# TX.net
KiCad netlist of a schematic drawn in EAGLE
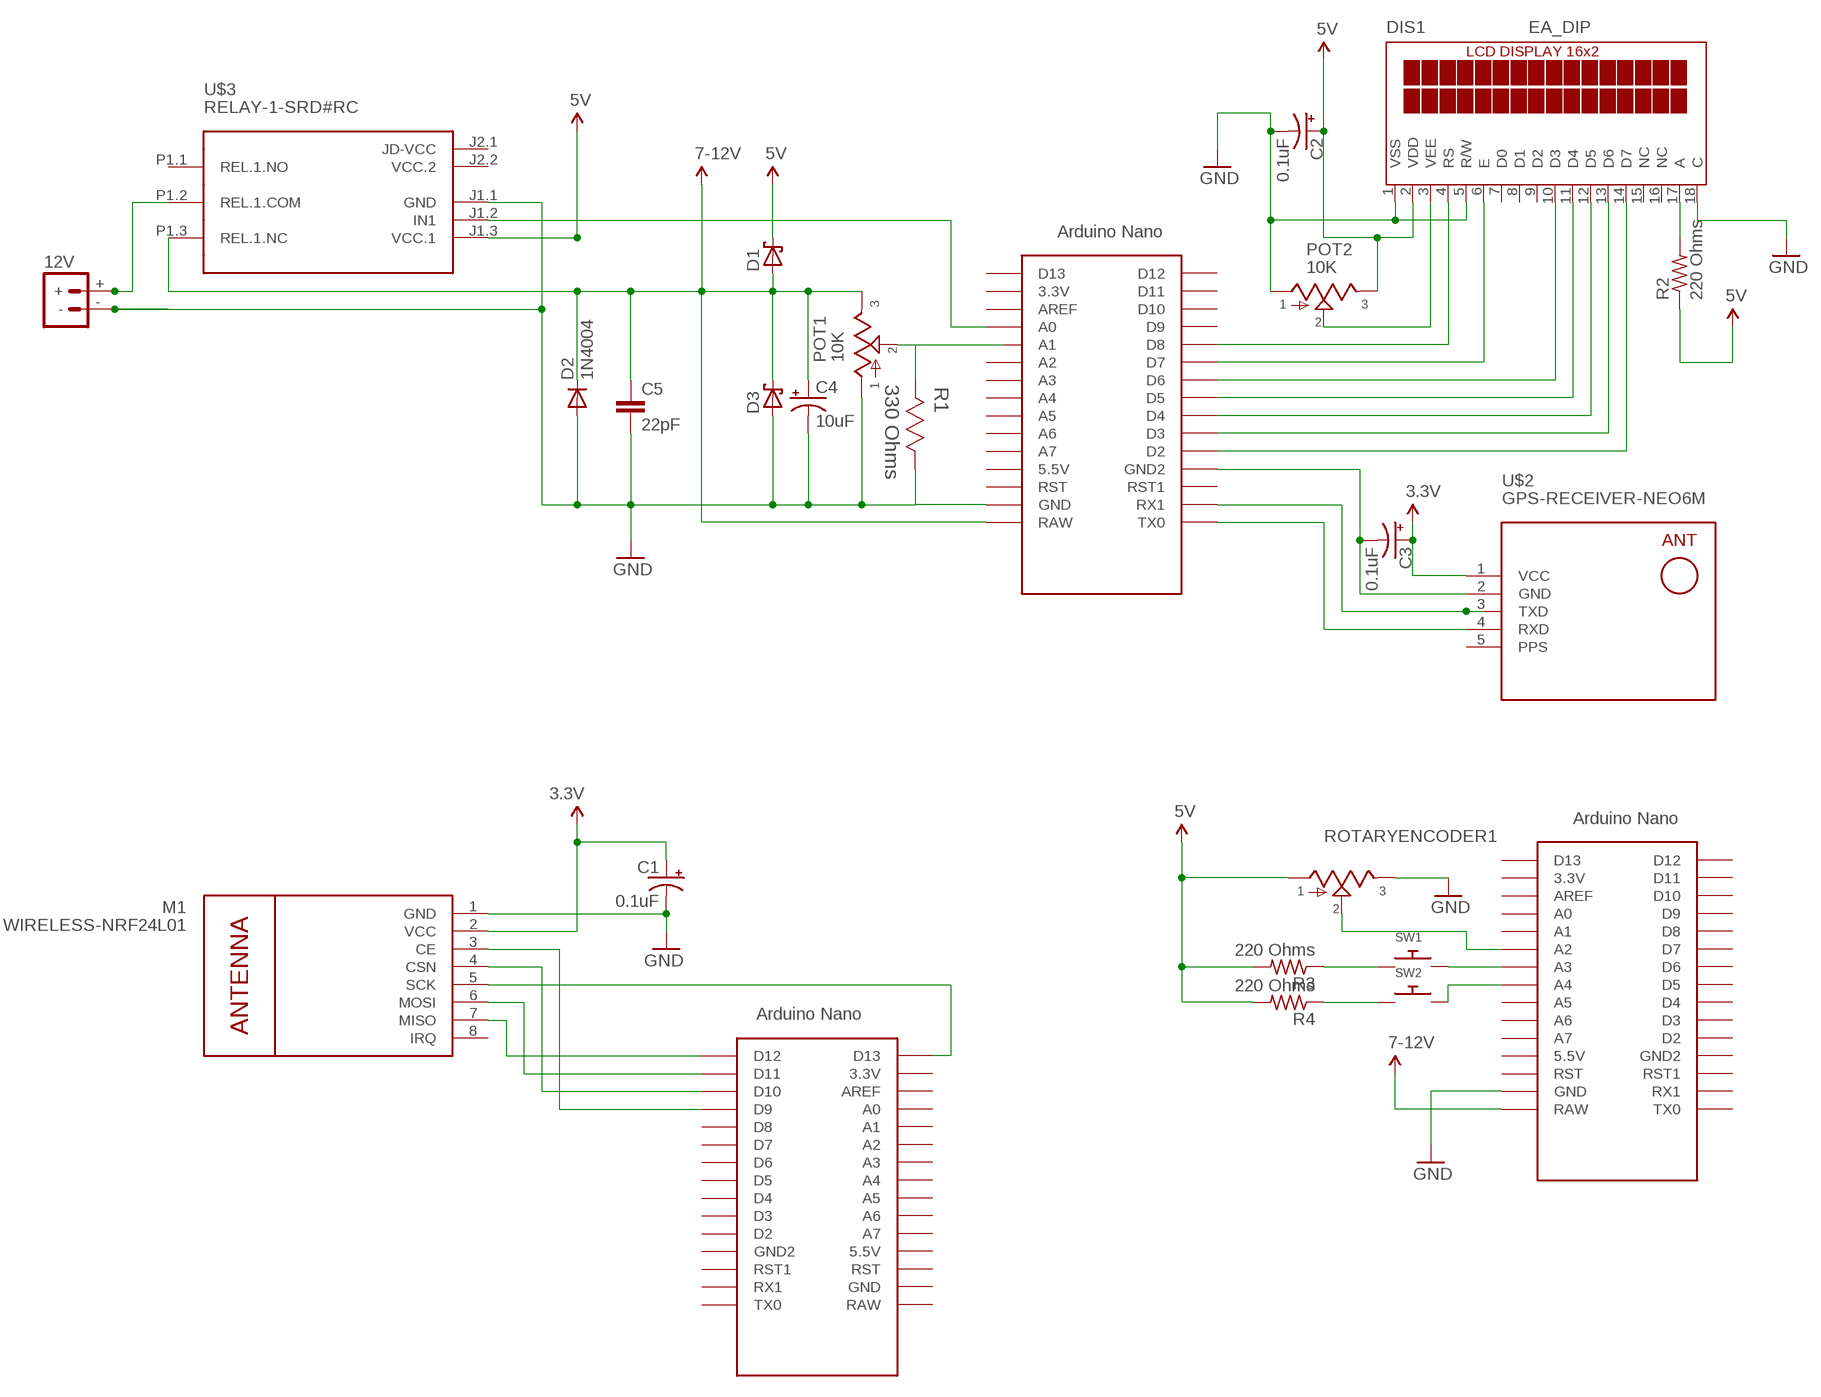
[diagram p0: schematic, sheet 1]

(export (version "E")
  (design (tool "Eeschema 10.0.6"))
  (components
    (comp (ref "12V")
      (value "BATTERY_CONN_DEANS")
      (footprint "eagle-import:DEANS")
      (libsource (lib "eagle-import") (part "BATTERY_CONN_DEANS"))
    )
    (comp (ref "C1")
      (value "0.1uF")
      (footprint "eagle-import:EIA3216")
      (libsource (lib "eagle-import") (part "10UF-16V-10%(TANT)"))
    )
    (comp (ref "C2")
      (value "0.1uF")
      (footprint "eagle-import:EIA3216")
      (libsource (lib "eagle-import") (part "10UF-16V-10%(TANT)"))
    )
    (comp (ref "C3")
      (value "0.1uF")
      (footprint "eagle-import:EIA3216")
      (libsource (lib "eagle-import") (part "10UF-16V-10%(TANT)"))
    )
    (comp (ref "C4")
      (value "10uF")
      (footprint "eagle-import:EIA3216")
      (libsource (lib "eagle-import") (part "10UF-16V-10%(TANT)"))
    )
    (comp (ref "C5")
      (value "22pF")
      (footprint "eagle-import:C2.5-3")
      (libsource (lib "eagle-import") (part "C2,5-3"))
    )
    (comp (ref "D1")
      (value "SCHOTTKY-DIODEAG")
      (footprint "eagle-import:AG")
      (libsource (lib "eagle-import") (part "SCHOTTKY-DIODEAG"))
    )
    (comp (ref "D2")
      (value "1N4004")
      (footprint "eagle-import:DO41-10")
      (libsource (lib "eagle-import") (part "1N4004"))
    )
    (comp (ref "D3")
      (value "SCHOTTKY-DIODEAG")
      (footprint "eagle-import:AG")
      (libsource (lib "eagle-import") (part "SCHOTTKY-DIODEAG"))
    )
    (comp (ref "DIS1")
      (value "EA_DIP")
      (footprint "eagle-import:EA_DIP")
      (libsource (lib "eagle-import") (part "EA_DIP"))
    )
    (comp (ref "M1")
      (value "WIRELESS-NRF24L01")
      (footprint "eagle-import:WIRELESS-NRF24L01")
      (libsource (lib "eagle-import") (part "WIRELESS-NRF24L01"))
    )
    (comp (ref "POT1")
      (value "10K")
      (footprint "eagle-import:POT")
      (libsource (lib "eagle-import") (part "POT"))
    )
    (comp (ref "POT2")
      (value "10K")
      (footprint "eagle-import:POT")
      (libsource (lib "eagle-import") (part "POT"))
    )
    (comp (ref "R1")
      (value "330 Ohms")
      (footprint "eagle-import:RESC1608X60N")
      (fields (field (name "MPN") "CPF0603F44K2C1") (field (name "TOLERANCE") "± 1%"))
      (libsource (lib "eagle-import") (part "CPF0603F44K2C1"))
    )
    (comp (ref "R2")
      (value "220 Ohms")
      (footprint "eagle-import:0204V")
      (libsource (lib "eagle-import") (part "R-US_0204/2V"))
    )
    (comp (ref "R3")
      (value "220 Ohms")
      (footprint "eagle-import:0204V")
      (libsource (lib "eagle-import") (part "R-US_0204/2V"))
    )
    (comp (ref "R4")
      (value "220 Ohms")
      (footprint "eagle-import:0204V")
      (libsource (lib "eagle-import") (part "R-US_0204/2V"))
    )
    (comp (ref "ROTARYENCODER1")
      (value "POT")
      (footprint "eagle-import:POT")
      (libsource (lib "eagle-import") (part "POT"))
    )
    (comp (ref "SW1")
      (value "SWITCH_PUSHBUTTONC&K_KSS")
      (footprint "eagle-import:BTN_CK_KSS")
      (libsource (lib "eagle-import") (part "SWITCH_PUSHBUTTONC&K_KSS"))
    )
    (comp (ref "SW2")
      (value "SWITCH_PUSHBUTTONC&K_KSS")
      (footprint "eagle-import:BTN_CK_KSS")
      (libsource (lib "eagle-import") (part "SWITCH_PUSHBUTTONC&K_KSS"))
    )
    (comp (ref "U$1")
      (value "NANO")
      (footprint "eagle-import:NANO")
      (libsource (lib "eagle-import") (part "NANO"))
    )
    (comp (ref "U$2")
      (value "GPS-RECEIVER-NEO6M")
      (footprint "eagle-import:GPS-RECEIVER-NEO6M")
      (libsource (lib "eagle-import") (part "GPS-RECEIVER-NEO6M"))
    )
    (comp (ref "U$3")
      (value "RELAY-1-SRD#RC")
      (footprint "eagle-import:RELAY-1-SRD#RC")
      (libsource (lib "eagle-import") (part "RELAY-1-SRD#RC"))
    )
    (comp (ref "U$4")
      (value "NANO")
      (footprint "eagle-import:NANO")
      (libsource (lib "eagle-import") (part "NANO"))
    )
    (comp (ref "U$5")
      (value "NANO")
      (footprint "eagle-import:NANO")
      (libsource (lib "eagle-import") (part "NANO"))
    )
  )
  (nets
    (net (code "1") (name "/PPS") (class "Default")
      (node (ref "U$2") (pin "5") (pinfunction "PPS_5") (pintype "power_in"))
    )
    (net (code "2") (name "/VCC.2") (class "Default")
      (node (ref "U$3") (pin "J2.2") (pinfunction "VCC.2_J2.2") (pintype "power_in"))
    )
    (net (code "3") (name "3.3V") (class "Default")
      (node (ref "C1") (pin "A") (pinfunction "+_A") (pintype "passive"))
      (node (ref "C2") (pin "A") (pinfunction "+_A") (pintype "passive"))
      (node (ref "C3") (pin "A") (pinfunction "+_A") (pintype "passive"))
      (node (ref "C4") (pin "A") (pinfunction "+_A") (pintype "passive"))
      (node (ref "C5") (pin "1") (pinfunction "1_1") (pintype "passive"))
      (node (ref "D1") (pin "A") (pinfunction "A_A") (pintype "passive"))
      (node (ref "D1") (pin "C") (pinfunction "C_C") (pintype "passive"))
      (node (ref "D2") (pin "C") (pinfunction "C_C") (pintype "passive"))
      (node (ref "D3") (pin "C") (pinfunction "C_C") (pintype "passive"))
      (node (ref "DIS1") (pin "2") (pinfunction "VDD_2") (pintype "power_in"))
      (node (ref "M1") (pin "2") (pinfunction "VCC_2") (pintype "power_in"))
      (node (ref "POT1") (pin "3") (pinfunction "3_3") (pintype "passive"))
      (node (ref "POT2") (pin "3") (pinfunction "3_3") (pintype "passive"))
      (node (ref "R2") (pin "1") (pinfunction "1_1") (pintype "passive"))
      (node (ref "R3") (pin "2") (pinfunction "2_2") (pintype "passive"))
      (node (ref "R4") (pin "2") (pinfunction "2_2") (pintype "passive"))
      (node (ref "ROTARYENCODER1") (pin "1") (pinfunction "1_1") (pintype "passive"))
      (node (ref "U$1") (pin "RAW") (pinfunction "RAW_RAW") (pintype "bidirectional"))
      (node (ref "U$2") (pin "1") (pinfunction "VCC_1") (pintype "bidirectional"))
      (node (ref "U$3") (pin "J1.3") (pinfunction "VCC.1_J1.3") (pintype "power_in"))
      (node (ref "U$3") (pin "P1.3") (pinfunction "REL.1.NC_P1.3") (pintype "bidirectional"))
      (node (ref "U$4") (pin "RAW") (pinfunction "RAW_RAW") (pintype "bidirectional"))
    )
    (net (code "4") (name "GND") (class "Default")
      (node (ref "12V") (pin "-") (pinfunction "-_-") (pintype "passive"))
      (node (ref "C1") (pin "C") (pinfunction "-_C") (pintype "passive"))
      (node (ref "C2") (pin "C") (pinfunction "-_C") (pintype "passive"))
      (node (ref "C4") (pin "C") (pinfunction "-_C") (pintype "passive"))
      (node (ref "C5") (pin "2") (pinfunction "2_2") (pintype "passive"))
      (node (ref "D2") (pin "A") (pinfunction "A_A") (pintype "passive"))
      (node (ref "D3") (pin "A") (pinfunction "A_A") (pintype "passive"))
      (node (ref "DIS1") (pin "1") (pinfunction "VSS_1") (pintype "power_in"))
      (node (ref "DIS1") (pin "18") (pinfunction "C_18") (pintype "passive"))
      (node (ref "DIS1") (pin "5") (pinfunction "R/W_5") (pintype "input"))
      (node (ref "M1") (pin "1") (pinfunction "GND_1") (pintype "power_in"))
      (node (ref "POT1") (pin "1") (pinfunction "1_1") (pintype "passive"))
      (node (ref "POT2") (pin "1") (pinfunction "1_1") (pintype "passive"))
      (node (ref "R1") (pin "1") (pinfunction "R1_1") (pintype "passive"))
      (node (ref "ROTARYENCODER1") (pin "3") (pinfunction "3_3") (pintype "passive"))
      (node (ref "U$1") (pin "GND") (pinfunction "GND_GND") (pintype "bidirectional"))
      (node (ref "U$3") (pin "J1.1") (pinfunction "GND_J1.1") (pintype "power_in"))
      (node (ref "U$4") (pin "GND") (pinfunction "GND_GND") (pintype "bidirectional"))
    )
    (net (code "5") (name "Net-(C3--)") (class "Default")
      (node (ref "C3") (pin "C") (pinfunction "-_C") (pintype "passive"))
      (node (ref "U$1") (pin "GND1") (pinfunction "GND2_GND1") (pintype "bidirectional"))
      (node (ref "U$2") (pin "2") (pinfunction "GND_2") (pintype "bidirectional"))
    )
    (net (code "6") (name "Net-(DIS1-A)") (class "Default")
      (node (ref "DIS1") (pin "17") (pinfunction "A_17") (pintype "passive"))
      (node (ref "R2") (pin "2") (pinfunction "2_2") (pintype "passive"))
    )
    (net (code "7") (name "Net-(DIS1-D3)") (class "Default")
      (node (ref "DIS1") (pin "10") (pinfunction "D3_10") (pintype "input"))
      (node (ref "U$1") (pin "D6") (pinfunction "D6_D6") (pintype "bidirectional"))
    )
    (net (code "8") (name "Net-(DIS1-D4)") (class "Default")
      (node (ref "DIS1") (pin "11") (pinfunction "D4_11") (pintype "input"))
      (node (ref "U$1") (pin "D5") (pinfunction "D5_D5") (pintype "bidirectional"))
    )
    (net (code "9") (name "Net-(DIS1-D5)") (class "Default")
      (node (ref "DIS1") (pin "12") (pinfunction "D5_12") (pintype "input"))
      (node (ref "U$1") (pin "D4") (pinfunction "D4_D4") (pintype "bidirectional"))
    )
    (net (code "10") (name "Net-(DIS1-D6)") (class "Default")
      (node (ref "DIS1") (pin "13") (pinfunction "D6_13") (pintype "input"))
      (node (ref "U$1") (pin "D3") (pinfunction "D3_D3") (pintype "bidirectional"))
    )
    (net (code "11") (name "Net-(DIS1-D7)") (class "Default")
      (node (ref "DIS1") (pin "14") (pinfunction "D7_14") (pintype "input"))
      (node (ref "U$1") (pin "D2") (pinfunction "D2_D2") (pintype "bidirectional"))
    )
    (net (code "12") (name "Net-(DIS1-E)") (class "Default")
      (node (ref "DIS1") (pin "6") (pinfunction "E_6") (pintype "input"))
      (node (ref "U$1") (pin "D7") (pinfunction "D7_D7") (pintype "bidirectional"))
    )
    (net (code "13") (name "Net-(DIS1-RS)") (class "Default")
      (node (ref "DIS1") (pin "4") (pinfunction "RS_4") (pintype "input"))
      (node (ref "U$1") (pin "D8") (pinfunction "D8_D8") (pintype "bidirectional"))
    )
    (net (code "14") (name "Net-(DIS1-VEE)") (class "Default")
      (node (ref "DIS1") (pin "3") (pinfunction "VEE_3") (pintype "power_in"))
      (node (ref "POT2") (pin "2") (pinfunction "2_2") (pintype "passive"))
    )
    (net (code "15") (name "Net-(M1-CE)") (class "Default")
      (node (ref "M1") (pin "3") (pinfunction "CE_3") (pintype "bidirectional"))
      (node (ref "U$5") (pin "D9") (pinfunction "D9_D9") (pintype "bidirectional"))
    )
    (net (code "16") (name "Net-(M1-CSN)") (class "Default")
      (node (ref "M1") (pin "4") (pinfunction "CSN_4") (pintype "bidirectional"))
      (node (ref "U$5") (pin "D10") (pinfunction "D10_D10") (pintype "bidirectional"))
    )
    (net (code "17") (name "Net-(M1-MISO)") (class "Default")
      (node (ref "M1") (pin "7") (pinfunction "MISO_7") (pintype "bidirectional"))
      (node (ref "U$5") (pin "D12") (pinfunction "D12_D12") (pintype "bidirectional"))
    )
    (net (code "18") (name "Net-(M1-MOSI)") (class "Default")
      (node (ref "M1") (pin "6") (pinfunction "MOSI_6") (pintype "bidirectional"))
      (node (ref "U$5") (pin "D11") (pinfunction "D11_D11") (pintype "bidirectional"))
    )
    (net (code "19") (name "Net-(M1-SCK)") (class "Default")
      (node (ref "M1") (pin "5") (pinfunction "SCK_5") (pintype "bidirectional"))
      (node (ref "U$5") (pin "D13") (pinfunction "D13_D13") (pintype "bidirectional"))
    )
    (net (code "20") (name "Net-(R1-R2)") (class "Default")
      (node (ref "POT1") (pin "2") (pinfunction "2_2") (pintype "passive"))
      (node (ref "R1") (pin "2") (pinfunction "R2_2") (pintype "passive"))
    )
    (net (code "21") (name "Net-(R3-Pad1)") (class "Default")
      (node (ref "R3") (pin "1") (pinfunction "1_1") (pintype "passive"))
      (node (ref "SW1") (pin "P$1") (pinfunction "P$1_P$1") (pintype "passive"))
    )
    (net (code "22") (name "Net-(R4-Pad1)") (class "Default")
      (node (ref "R4") (pin "1") (pinfunction "1_1") (pintype "passive"))
      (node (ref "SW2") (pin "P$1") (pinfunction "P$1_P$1") (pintype "passive"))
    )
    (net (code "23") (name "Net-(ROTARYENCODER1-Pad2)") (class "Default")
      (node (ref "ROTARYENCODER1") (pin "2") (pinfunction "2_2") (pintype "passive"))
      (node (ref "U$4") (pin "A2") (pinfunction "A2_A2") (pintype "bidirectional"))
    )
    (net (code "24") (name "Net-(SW1-PadP$2)") (class "Default")
      (node (ref "SW1") (pin "P$2") (pinfunction "P$2_P$2") (pintype "passive"))
      (node (ref "U$4") (pin "A3") (pinfunction "A3_A3") (pintype "bidirectional"))
    )
    (net (code "25") (name "Net-(SW2-PadP$2)") (class "Default")
      (node (ref "SW2") (pin "P$2") (pinfunction "P$2_P$2") (pintype "passive"))
      (node (ref "U$4") (pin "A4") (pinfunction "A4_A4") (pintype "bidirectional"))
    )
    (net (code "26") (name "Net-(U$2-RXD)") (class "Default")
      (node (ref "U$1") (pin "TX0") (pinfunction "TX0_TX0") (pintype "bidirectional"))
      (node (ref "U$2") (pin "4") (pinfunction "RXD_4") (pintype "power_in"))
    )
    (net (code "27") (name "Net-(U$2-TXD)") (class "Default")
      (node (ref "U$1") (pin "RX1") (pinfunction "RX1_RX1") (pintype "bidirectional"))
      (node (ref "U$2") (pin "3") (pinfunction "TXD_3") (pintype "bidirectional"))
    )
    (net (code "28") (name "Net-(U$3-IN1)") (class "Default")
      (node (ref "U$1") (pin "A0") (pinfunction "A0_A0") (pintype "bidirectional"))
      (node (ref "U$3") (pin "J1.2") (pinfunction "IN1_J1.2") (pintype "bidirectional"))
    )
    (net (code "29") (name "Net-(U$3-REL.1.COM)") (class "Default")
      (node (ref "12V") (pin "+") (pinfunction "+_+") (pintype "passive"))
      (node (ref "U$3") (pin "P1.2") (pinfunction "REL.1.COM_P1.2") (pintype "bidirectional"))
    )
    (net (code "30") (name "unconnected-(DIS1-D0-Pad7)") (class "Default")
      (node (ref "DIS1") (pin "7") (pinfunction "D0_7") (pintype "input"))
    )
    (net (code "31") (name "unconnected-(DIS1-D1-Pad8)") (class "Default")
      (node (ref "DIS1") (pin "8") (pinfunction "D1_8") (pintype "input"))
    )
    (net (code "32") (name "unconnected-(DIS1-D2-Pad9)") (class "Default")
      (node (ref "DIS1") (pin "9") (pinfunction "D2_9") (pintype "input"))
    )
    (net (code "33") (name "unconnected-(DIS1-NC-Pad15)") (class "Default")
      (node (ref "DIS1") (pin "15") (pinfunction "NC_15") (pintype "no_connect"))
    )
    (net (code "34") (name "unconnected-(DIS1-NC-Pad16)") (class "Default")
      (node (ref "DIS1") (pin "16") (pinfunction "NC_16") (pintype "no_connect"))
    )
    (net (code "35") (name "unconnected-(M1-IRQ-Pad8)") (class "Default")
      (node (ref "M1") (pin "8") (pinfunction "IRQ_8") (pintype "bidirectional"))
    )
    (net (code "36") (name "unconnected-(U$1-5.5V-Pad5V)") (class "Default")
      (node (ref "U$1") (pin "5V") (pinfunction "5.5V_5V") (pintype "bidirectional"))
    )
    (net (code "37") (name "unconnected-(U$1-Pad3.3V)") (class "Default")
      (node (ref "U$1") (pin "3.3V") (pinfunction "3.3V_3.3V") (pintype "bidirectional"))
    )
    (net (code "38") (name "unconnected-(U$1-PadA1)") (class "Default")
      (node (ref "U$1") (pin "A1") (pinfunction "A1_A1") (pintype "bidirectional"))
    )
    (net (code "39") (name "unconnected-(U$1-PadA2)") (class "Default")
      (node (ref "U$1") (pin "A2") (pinfunction "A2_A2") (pintype "bidirectional"))
    )
    (net (code "40") (name "unconnected-(U$1-PadA3)") (class "Default")
      (node (ref "U$1") (pin "A3") (pinfunction "A3_A3") (pintype "bidirectional"))
    )
    (net (code "41") (name "unconnected-(U$1-PadA4)") (class "Default")
      (node (ref "U$1") (pin "A4") (pinfunction "A4_A4") (pintype "bidirectional"))
    )
    (net (code "42") (name "unconnected-(U$1-PadA5)") (class "Default")
      (node (ref "U$1") (pin "A5") (pinfunction "A5_A5") (pintype "bidirectional"))
    )
    (net (code "43") (name "unconnected-(U$1-PadA6)") (class "Default")
      (node (ref "U$1") (pin "A6") (pinfunction "A6_A6") (pintype "bidirectional"))
    )
    (net (code "44") (name "unconnected-(U$1-PadA7)") (class "Default")
      (node (ref "U$1") (pin "A7") (pinfunction "A7_A7") (pintype "bidirectional"))
    )
    (net (code "45") (name "unconnected-(U$1-PadAREF)") (class "Default")
      (node (ref "U$1") (pin "AREF") (pinfunction "AREF_AREF") (pintype "bidirectional"))
    )
    (net (code "46") (name "unconnected-(U$1-PadD9)") (class "Default")
      (node (ref "U$1") (pin "D9") (pinfunction "D9_D9") (pintype "bidirectional"))
    )
    (net (code "47") (name "unconnected-(U$1-PadD10)") (class "Default")
      (node (ref "U$1") (pin "D10") (pinfunction "D10_D10") (pintype "bidirectional"))
    )
    (net (code "48") (name "unconnected-(U$1-PadD11)") (class "Default")
      (node (ref "U$1") (pin "D11") (pinfunction "D11_D11") (pintype "bidirectional"))
    )
    (net (code "49") (name "unconnected-(U$1-PadD12)") (class "Default")
      (node (ref "U$1") (pin "D12") (pinfunction "D12_D12") (pintype "bidirectional"))
    )
    (net (code "50") (name "unconnected-(U$1-PadD13)") (class "Default")
      (node (ref "U$1") (pin "D13") (pinfunction "D13_D13") (pintype "bidirectional"))
    )
    (net (code "51") (name "unconnected-(U$1-PadICSP1)") (class "Default")
      (node (ref "U$1") (pin "ICSP1") (pinfunction "ICSP1_ICSP1") (pintype "bidirectional"))
    )
    (net (code "52") (name "unconnected-(U$1-PadICSP2)") (class "Default")
      (node (ref "U$1") (pin "ICSP2") (pinfunction "ICSP2_ICSP2") (pintype "bidirectional"))
    )
    (net (code "53") (name "unconnected-(U$1-PadICSP3)") (class "Default")
      (node (ref "U$1") (pin "ICSP3") (pinfunction "ICSP3_ICSP3") (pintype "bidirectional"))
    )
    (net (code "54") (name "unconnected-(U$1-PadICSP4)") (class "Default")
      (node (ref "U$1") (pin "ICSP4") (pinfunction "ICSP4_ICSP4") (pintype "bidirectional"))
    )
    (net (code "55") (name "unconnected-(U$1-PadICSP5)") (class "Default")
      (node (ref "U$1") (pin "ICSP5") (pinfunction "ICSP5_ICSP5") (pintype "bidirectional"))
    )
    (net (code "56") (name "unconnected-(U$1-PadICSP6)") (class "Default")
      (node (ref "U$1") (pin "ICSP6") (pinfunction "ICSP6_ICSP6") (pintype "bidirectional"))
    )
    (net (code "57") (name "unconnected-(U$1-PadRST)") (class "Default")
      (node (ref "U$1") (pin "RST") (pinfunction "RST_RST") (pintype "bidirectional"))
    )
    (net (code "58") (name "unconnected-(U$1-PadRST1)") (class "Default")
      (node (ref "U$1") (pin "RST1") (pinfunction "RST1_RST1") (pintype "bidirectional"))
    )
    (net (code "59") (name "unconnected-(U$3-JD-VCC-PadJ2.1)") (class "Default")
      (node (ref "U$3") (pin "J2.1") (pinfunction "JD-VCC_J2.1") (pintype "bidirectional"))
    )
    (net (code "60") (name "unconnected-(U$3-REL.1.NO-PadP1.1)") (class "Default")
      (node (ref "U$3") (pin "P1.1") (pinfunction "REL.1.NO_P1.1") (pintype "bidirectional"))
    )
    (net (code "61") (name "unconnected-(U$4-5.5V-Pad5V)") (class "Default")
      (node (ref "U$4") (pin "5V") (pinfunction "5.5V_5V") (pintype "bidirectional"))
    )
    (net (code "62") (name "unconnected-(U$4-GND2-PadGND1)") (class "Default")
      (node (ref "U$4") (pin "GND1") (pinfunction "GND2_GND1") (pintype "bidirectional"))
    )
    (net (code "63") (name "unconnected-(U$4-Pad3.3V)") (class "Default")
      (node (ref "U$4") (pin "3.3V") (pinfunction "3.3V_3.3V") (pintype "bidirectional"))
    )
    (net (code "64") (name "unconnected-(U$4-PadA0)") (class "Default")
      (node (ref "U$4") (pin "A0") (pinfunction "A0_A0") (pintype "bidirectional"))
    )
    (net (code "65") (name "unconnected-(U$4-PadA1)") (class "Default")
      (node (ref "U$4") (pin "A1") (pinfunction "A1_A1") (pintype "bidirectional"))
    )
    (net (code "66") (name "unconnected-(U$4-PadA5)") (class "Default")
      (node (ref "U$4") (pin "A5") (pinfunction "A5_A5") (pintype "bidirectional"))
    )
    (net (code "67") (name "unconnected-(U$4-PadA6)") (class "Default")
      (node (ref "U$4") (pin "A6") (pinfunction "A6_A6") (pintype "bidirectional"))
    )
    (net (code "68") (name "unconnected-(U$4-PadA7)") (class "Default")
      (node (ref "U$4") (pin "A7") (pinfunction "A7_A7") (pintype "bidirectional"))
    )
    (net (code "69") (name "unconnected-(U$4-PadAREF)") (class "Default")
      (node (ref "U$4") (pin "AREF") (pinfunction "AREF_AREF") (pintype "bidirectional"))
    )
    (net (code "70") (name "unconnected-(U$4-PadD2)") (class "Default")
      (node (ref "U$4") (pin "D2") (pinfunction "D2_D2") (pintype "bidirectional"))
    )
    (net (code "71") (name "unconnected-(U$4-PadD3)") (class "Default")
      (node (ref "U$4") (pin "D3") (pinfunction "D3_D3") (pintype "bidirectional"))
    )
    (net (code "72") (name "unconnected-(U$4-PadD4)") (class "Default")
      (node (ref "U$4") (pin "D4") (pinfunction "D4_D4") (pintype "bidirectional"))
    )
    (net (code "73") (name "unconnected-(U$4-PadD5)") (class "Default")
      (node (ref "U$4") (pin "D5") (pinfunction "D5_D5") (pintype "bidirectional"))
    )
    (net (code "74") (name "unconnected-(U$4-PadD6)") (class "Default")
      (node (ref "U$4") (pin "D6") (pinfunction "D6_D6") (pintype "bidirectional"))
    )
    (net (code "75") (name "unconnected-(U$4-PadD7)") (class "Default")
      (node (ref "U$4") (pin "D7") (pinfunction "D7_D7") (pintype "bidirectional"))
    )
    (net (code "76") (name "unconnected-(U$4-PadD8)") (class "Default")
      (node (ref "U$4") (pin "D8") (pinfunction "D8_D8") (pintype "bidirectional"))
    )
    (net (code "77") (name "unconnected-(U$4-PadD9)") (class "Default")
      (node (ref "U$4") (pin "D9") (pinfunction "D9_D9") (pintype "bidirectional"))
    )
    (net (code "78") (name "unconnected-(U$4-PadD10)") (class "Default")
      (node (ref "U$4") (pin "D10") (pinfunction "D10_D10") (pintype "bidirectional"))
    )
    (net (code "79") (name "unconnected-(U$4-PadD11)") (class "Default")
      (node (ref "U$4") (pin "D11") (pinfunction "D11_D11") (pintype "bidirectional"))
    )
    (net (code "80") (name "unconnected-(U$4-PadD12)") (class "Default")
      (node (ref "U$4") (pin "D12") (pinfunction "D12_D12") (pintype "bidirectional"))
    )
    (net (code "81") (name "unconnected-(U$4-PadD13)") (class "Default")
      (node (ref "U$4") (pin "D13") (pinfunction "D13_D13") (pintype "bidirectional"))
    )
    (net (code "82") (name "unconnected-(U$4-PadICSP1)") (class "Default")
      (node (ref "U$4") (pin "ICSP1") (pinfunction "ICSP1_ICSP1") (pintype "bidirectional"))
    )
    (net (code "83") (name "unconnected-(U$4-PadICSP2)") (class "Default")
      (node (ref "U$4") (pin "ICSP2") (pinfunction "ICSP2_ICSP2") (pintype "bidirectional"))
    )
    (net (code "84") (name "unconnected-(U$4-PadICSP3)") (class "Default")
      (node (ref "U$4") (pin "ICSP3") (pinfunction "ICSP3_ICSP3") (pintype "bidirectional"))
    )
    (net (code "85") (name "unconnected-(U$4-PadICSP4)") (class "Default")
      (node (ref "U$4") (pin "ICSP4") (pinfunction "ICSP4_ICSP4") (pintype "bidirectional"))
    )
    (net (code "86") (name "unconnected-(U$4-PadICSP5)") (class "Default")
      (node (ref "U$4") (pin "ICSP5") (pinfunction "ICSP5_ICSP5") (pintype "bidirectional"))
    )
    (net (code "87") (name "unconnected-(U$4-PadICSP6)") (class "Default")
      (node (ref "U$4") (pin "ICSP6") (pinfunction "ICSP6_ICSP6") (pintype "bidirectional"))
    )
    (net (code "88") (name "unconnected-(U$4-PadRST)") (class "Default")
      (node (ref "U$4") (pin "RST") (pinfunction "RST_RST") (pintype "bidirectional"))
    )
    (net (code "89") (name "unconnected-(U$4-PadRST1)") (class "Default")
      (node (ref "U$4") (pin "RST1") (pinfunction "RST1_RST1") (pintype "bidirectional"))
    )
    (net (code "90") (name "unconnected-(U$4-PadRX1)") (class "Default")
      (node (ref "U$4") (pin "RX1") (pinfunction "RX1_RX1") (pintype "bidirectional"))
    )
    (net (code "91") (name "unconnected-(U$4-PadTX0)") (class "Default")
      (node (ref "U$4") (pin "TX0") (pinfunction "TX0_TX0") (pintype "bidirectional"))
    )
    (net (code "92") (name "unconnected-(U$5-5.5V-Pad5V)") (class "Default")
      (node (ref "U$5") (pin "5V") (pinfunction "5.5V_5V") (pintype "bidirectional"))
    )
    (net (code "93") (name "unconnected-(U$5-GND2-PadGND1)") (class "Default")
      (node (ref "U$5") (pin "GND1") (pinfunction "GND2_GND1") (pintype "bidirectional"))
    )
    (net (code "94") (name "unconnected-(U$5-Pad3.3V)") (class "Default")
      (node (ref "U$5") (pin "3.3V") (pinfunction "3.3V_3.3V") (pintype "bidirectional"))
    )
    (net (code "95") (name "unconnected-(U$5-PadA0)") (class "Default")
      (node (ref "U$5") (pin "A0") (pinfunction "A0_A0") (pintype "bidirectional"))
    )
    (net (code "96") (name "unconnected-(U$5-PadA1)") (class "Default")
      (node (ref "U$5") (pin "A1") (pinfunction "A1_A1") (pintype "bidirectional"))
    )
    (net (code "97") (name "unconnected-(U$5-PadA2)") (class "Default")
      (node (ref "U$5") (pin "A2") (pinfunction "A2_A2") (pintype "bidirectional"))
    )
    (net (code "98") (name "unconnected-(U$5-PadA3)") (class "Default")
      (node (ref "U$5") (pin "A3") (pinfunction "A3_A3") (pintype "bidirectional"))
    )
    (net (code "99") (name "unconnected-(U$5-PadA4)") (class "Default")
      (node (ref "U$5") (pin "A4") (pinfunction "A4_A4") (pintype "bidirectional"))
    )
    (net (code "100") (name "unconnected-(U$5-PadA5)") (class "Default")
      (node (ref "U$5") (pin "A5") (pinfunction "A5_A5") (pintype "bidirectional"))
    )
    (net (code "101") (name "unconnected-(U$5-PadA6)") (class "Default")
      (node (ref "U$5") (pin "A6") (pinfunction "A6_A6") (pintype "bidirectional"))
    )
    (net (code "102") (name "unconnected-(U$5-PadA7)") (class "Default")
      (node (ref "U$5") (pin "A7") (pinfunction "A7_A7") (pintype "bidirectional"))
    )
    (net (code "103") (name "unconnected-(U$5-PadAREF)") (class "Default")
      (node (ref "U$5") (pin "AREF") (pinfunction "AREF_AREF") (pintype "bidirectional"))
    )
    (net (code "104") (name "unconnected-(U$5-PadD2)") (class "Default")
      (node (ref "U$5") (pin "D2") (pinfunction "D2_D2") (pintype "bidirectional"))
    )
    (net (code "105") (name "unconnected-(U$5-PadD3)") (class "Default")
      (node (ref "U$5") (pin "D3") (pinfunction "D3_D3") (pintype "bidirectional"))
    )
    (net (code "106") (name "unconnected-(U$5-PadD4)") (class "Default")
      (node (ref "U$5") (pin "D4") (pinfunction "D4_D4") (pintype "bidirectional"))
    )
    (net (code "107") (name "unconnected-(U$5-PadD5)") (class "Default")
      (node (ref "U$5") (pin "D5") (pinfunction "D5_D5") (pintype "bidirectional"))
    )
    (net (code "108") (name "unconnected-(U$5-PadD6)") (class "Default")
      (node (ref "U$5") (pin "D6") (pinfunction "D6_D6") (pintype "bidirectional"))
    )
    (net (code "109") (name "unconnected-(U$5-PadD7)") (class "Default")
      (node (ref "U$5") (pin "D7") (pinfunction "D7_D7") (pintype "bidirectional"))
    )
    (net (code "110") (name "unconnected-(U$5-PadD8)") (class "Default")
      (node (ref "U$5") (pin "D8") (pinfunction "D8_D8") (pintype "bidirectional"))
    )
    (net (code "111") (name "unconnected-(U$5-PadGND)") (class "Default")
      (node (ref "U$5") (pin "GND") (pinfunction "GND_GND") (pintype "bidirectional"))
    )
    (net (code "112") (name "unconnected-(U$5-PadICSP1)") (class "Default")
      (node (ref "U$5") (pin "ICSP1") (pinfunction "ICSP1_ICSP1") (pintype "bidirectional"))
    )
    (net (code "113") (name "unconnected-(U$5-PadICSP2)") (class "Default")
      (node (ref "U$5") (pin "ICSP2") (pinfunction "ICSP2_ICSP2") (pintype "bidirectional"))
    )
    (net (code "114") (name "unconnected-(U$5-PadICSP3)") (class "Default")
      (node (ref "U$5") (pin "ICSP3") (pinfunction "ICSP3_ICSP3") (pintype "bidirectional"))
    )
    (net (code "115") (name "unconnected-(U$5-PadICSP4)") (class "Default")
      (node (ref "U$5") (pin "ICSP4") (pinfunction "ICSP4_ICSP4") (pintype "bidirectional"))
    )
    (net (code "116") (name "unconnected-(U$5-PadICSP5)") (class "Default")
      (node (ref "U$5") (pin "ICSP5") (pinfunction "ICSP5_ICSP5") (pintype "bidirectional"))
    )
    (net (code "117") (name "unconnected-(U$5-PadICSP6)") (class "Default")
      (node (ref "U$5") (pin "ICSP6") (pinfunction "ICSP6_ICSP6") (pintype "bidirectional"))
    )
    (net (code "118") (name "unconnected-(U$5-PadRAW)") (class "Default")
      (node (ref "U$5") (pin "RAW") (pinfunction "RAW_RAW") (pintype "bidirectional"))
    )
    (net (code "119") (name "unconnected-(U$5-PadRST)") (class "Default")
      (node (ref "U$5") (pin "RST") (pinfunction "RST_RST") (pintype "bidirectional"))
    )
    (net (code "120") (name "unconnected-(U$5-PadRST1)") (class "Default")
      (node (ref "U$5") (pin "RST1") (pinfunction "RST1_RST1") (pintype "bidirectional"))
    )
    (net (code "121") (name "unconnected-(U$5-PadRX1)") (class "Default")
      (node (ref "U$5") (pin "RX1") (pinfunction "RX1_RX1") (pintype "bidirectional"))
    )
    (net (code "122") (name "unconnected-(U$5-PadTX0)") (class "Default")
      (node (ref "U$5") (pin "TX0") (pinfunction "TX0_TX0") (pintype "bidirectional"))
    )
  )
)
